# maido_board.net
KiCad netlist of a schematic drawn in EAGLE
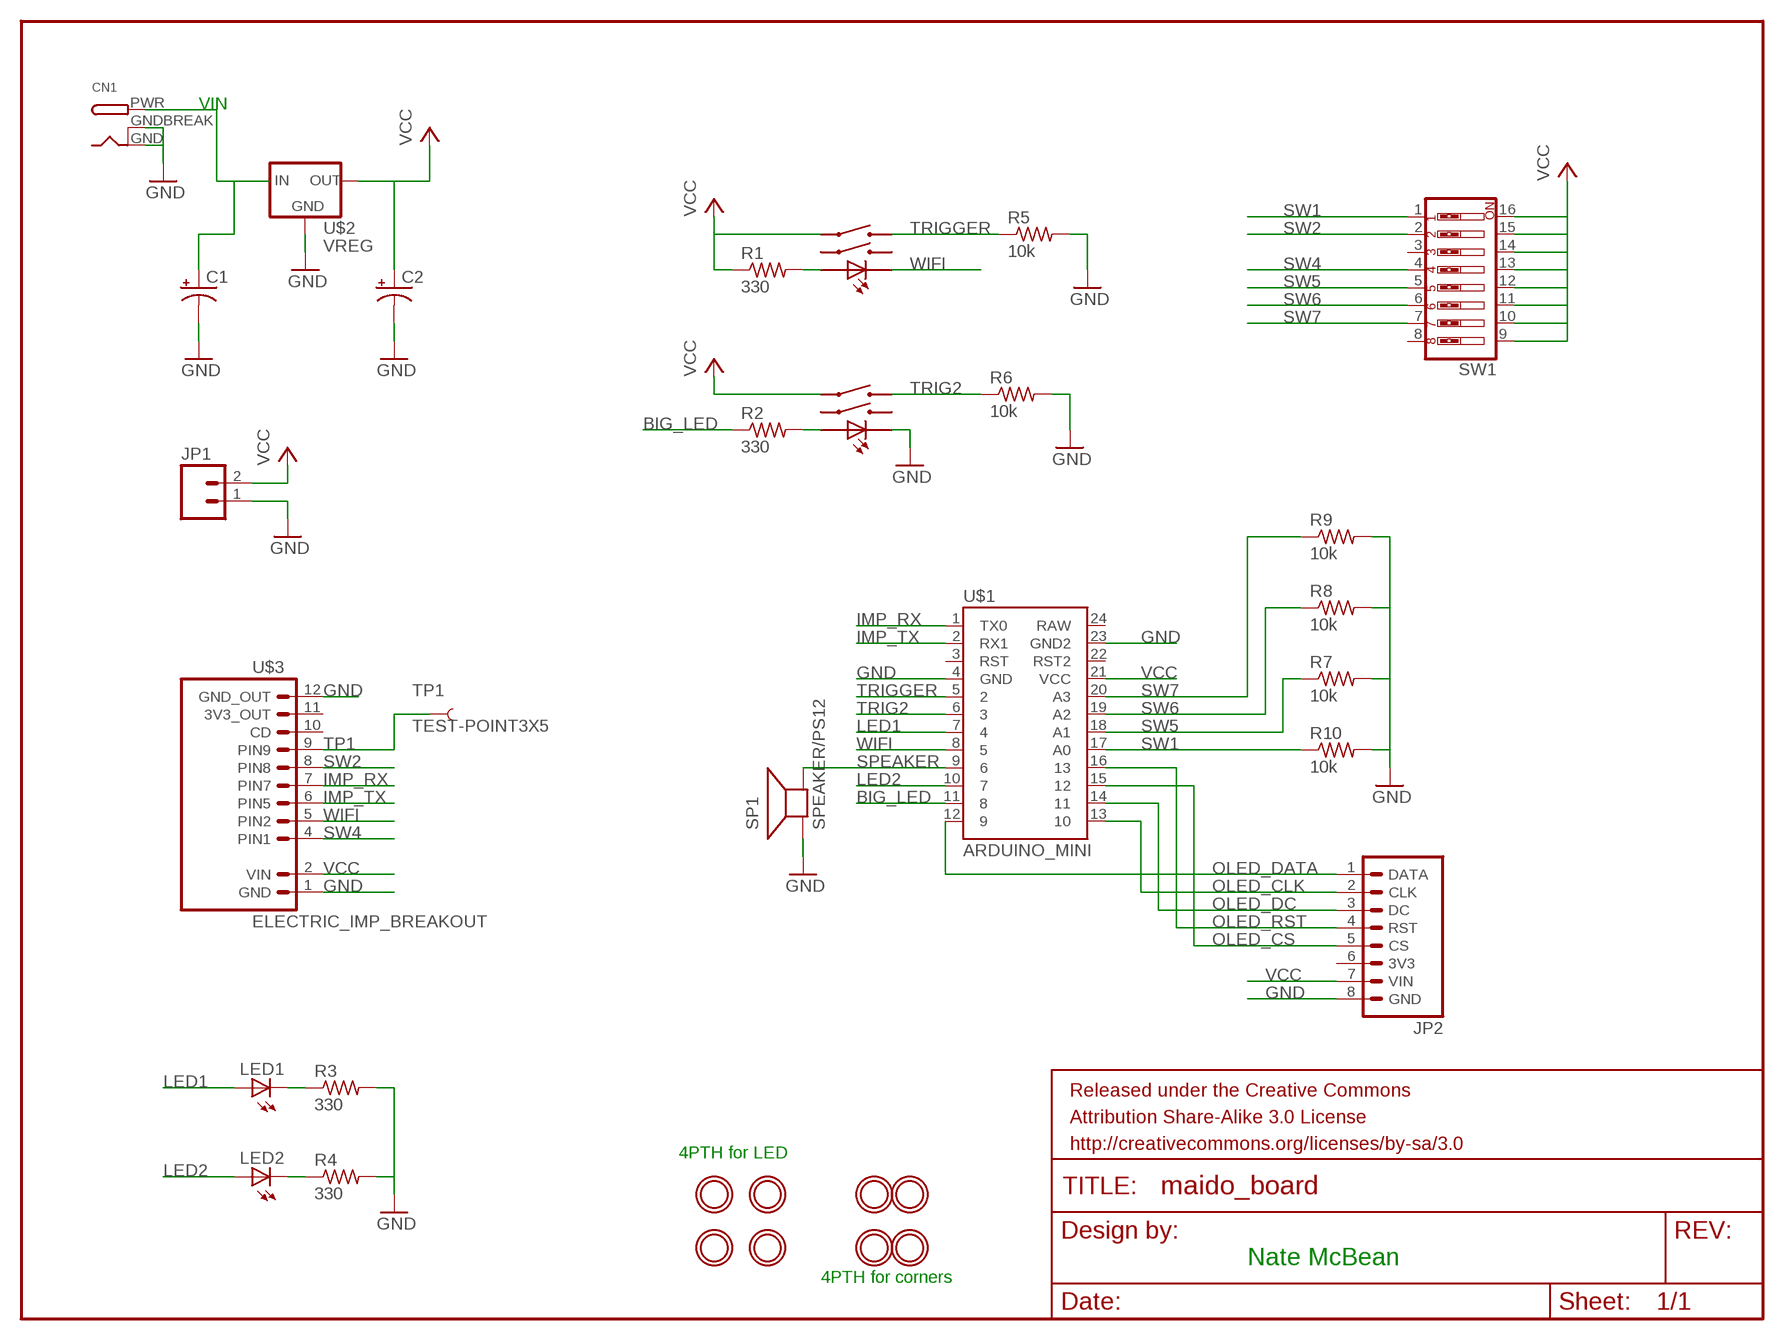
[diagram p0: schematic, sheet 1]

(export (version "E")
  (design (tool "Eeschema 10.0.6"))
  (components
    (comp (ref "ACK")
      (value "LED_TACTILE_BUTTON")
      (footprint "eagle-import:LED_TACTILE_BUTTON")
      (libsource (lib "eagle-import") (part "LED_TACTILE_BUTTON"))
    )
    (comp (ref "C1")
      (value "CAP_POLPTH2")
      (footprint "eagle-import:CPOL-RADIAL-10UF-25V")
      (libsource (lib "eagle-import") (part "CAP_POLPTH2"))
    )
    (comp (ref "C2")
      (value "CAP_POLPTH2")
      (footprint "eagle-import:CPOL-RADIAL-10UF-25V")
      (libsource (lib "eagle-import") (part "CAP_POLPTH2"))
    )
    (comp (ref "CN1")
      (value "DCBARRELPTH")
      (footprint "eagle-import:DCJACK_2MM_PTH")
      (libsource (lib "eagle-import") (part "DCBARRELPTH"))
    )
    (comp (ref "FRAME1")
      (value "FRAME-LETTER")
      (footprint "eagle-import:CREATIVE_COMMONS")
      (libsource (lib "eagle-import") (part "FRAME-LETTER"))
    )
    (comp (ref "JP1")
      (value "M02PTH")
      (footprint "eagle-import:1X02")
      (libsource (lib "eagle-import") (part "M02PTH"))
    )
    (comp (ref "JP2")
      (value "OLED128X641X08")
      (footprint "eagle-import:OLED_128X64")
      (libsource (lib "eagle-import") (part "OLED128X641X08"))
    )
    (comp (ref "LED1")
      (value "LED5MM")
      (footprint "eagle-import:LED5MM")
      (libsource (lib "eagle-import") (part "LED5MM"))
    )
    (comp (ref "LED2")
      (value "LED5MM")
      (footprint "eagle-import:LED5MM")
      (libsource (lib "eagle-import") (part "LED5MM"))
    )
    (comp (ref "R1")
      (value "330")
      (footprint "eagle-import:R0805")
      (libsource (lib "eagle-import") (part "R-US_R0805"))
    )
    (comp (ref "R2")
      (value "330")
      (footprint "eagle-import:R0805")
      (libsource (lib "eagle-import") (part "R-US_R0805"))
    )
    (comp (ref "R3")
      (value "330")
      (footprint "eagle-import:R0805")
      (libsource (lib "eagle-import") (part "R-US_R0805"))
    )
    (comp (ref "R4")
      (value "330")
      (footprint "eagle-import:R0805")
      (libsource (lib "eagle-import") (part "R-US_R0805"))
    )
    (comp (ref "R5")
      (value "10k")
      (footprint "eagle-import:R0805")
      (libsource (lib "eagle-import") (part "R-US_R0805"))
    )
    (comp (ref "R6")
      (value "10k")
      (footprint "eagle-import:R0805")
      (libsource (lib "eagle-import") (part "R-US_R0805"))
    )
    (comp (ref "R7")
      (value "10k")
      (footprint "eagle-import:R0805")
      (libsource (lib "eagle-import") (part "R-US_R0805"))
    )
    (comp (ref "R8")
      (value "10k")
      (footprint "eagle-import:R0805")
      (libsource (lib "eagle-import") (part "R-US_R0805"))
    )
    (comp (ref "R9")
      (value "10k")
      (footprint "eagle-import:R0805")
      (libsource (lib "eagle-import") (part "R-US_R0805"))
    )
    (comp (ref "R10")
      (value "10k")
      (footprint "eagle-import:R0805")
      (libsource (lib "eagle-import") (part "R-US_R0805"))
    )
    (comp (ref "SEND")
      (value "LED_TACTILE_BUTTON")
      (footprint "eagle-import:LED_TACTILE_BUTTON")
      (libsource (lib "eagle-import") (part "LED_TACTILE_BUTTON"))
    )
    (comp (ref "SP1")
      (value "SPEAKER/PS12")
      (footprint "eagle-import:PS12")
      (libsource (lib "eagle-import") (part "SPEAKER/PS12"))
    )
    (comp (ref "SW1")
      (value "SW_DIP-8")
      (footprint "eagle-import:DIPSWITCH-08")
      (libsource (lib "eagle-import") (part "SW_DIP-8"))
    )
    (comp (ref "TP1")
      (value "TEST-POINT3X5")
      (footprint "eagle-import:PAD.03X.05")
      (libsource (lib "eagle-import") (part "TEST-POINT3X5"))
    )
    (comp (ref "U$1")
      (value "ARDUINO_MINI")
      (footprint "eagle-import:ARDUINO_MINI")
      (libsource (lib "eagle-import") (part "ARDUINO_MINI"))
    )
    (comp (ref "U$2")
      (value "VREG")
      (footprint "eagle-import:78XXL")
      (libsource (lib "eagle-import") (part "V_REG_LD1117VXX"))
    )
    (comp (ref "U$3")
      (value "ELECTRIC_IMP_BREAKOUT")
      (footprint "eagle-import:ELECTRIC_IMP_BREAKOUT")
      (libsource (lib "eagle-import") (part "ELECTRIC_IMP_BREAKOUT"))
    )
    (comp (ref "U$5")
      (value "MOUNTINGHOLE2.5")
      (footprint "eagle-import:MOUNTINGHOLE_2.5_PLATED")
      (libsource (lib "eagle-import") (part "MOUNTINGHOLE2.5"))
    )
    (comp (ref "U$6")
      (value "MOUNTINGHOLE2.5")
      (footprint "eagle-import:MOUNTINGHOLE_2.5_PLATED")
      (libsource (lib "eagle-import") (part "MOUNTINGHOLE2.5"))
    )
    (comp (ref "U$7")
      (value "MOUNTINGHOLE2.5")
      (footprint "eagle-import:MOUNTINGHOLE_2.5_PLATED")
      (libsource (lib "eagle-import") (part "MOUNTINGHOLE2.5"))
    )
    (comp (ref "U$8")
      (value "MOUNTINGHOLE2.5")
      (footprint "eagle-import:MOUNTINGHOLE_2.5_PLATED")
      (libsource (lib "eagle-import") (part "MOUNTINGHOLE2.5"))
    )
    (comp (ref "U$9")
      (value "MOUNTINGHOLE2.5")
      (footprint "eagle-import:MOUNTINGHOLE_2.5_PLATED")
      (libsource (lib "eagle-import") (part "MOUNTINGHOLE2.5"))
    )
    (comp (ref "U$10")
      (value "MOUNTINGHOLE2.5")
      (footprint "eagle-import:MOUNTINGHOLE_2.5_PLATED")
      (libsource (lib "eagle-import") (part "MOUNTINGHOLE2.5"))
    )
    (comp (ref "U$11")
      (value "MOUNTINGHOLE2.5")
      (footprint "eagle-import:MOUNTINGHOLE_2.5_PLATED")
      (libsource (lib "eagle-import") (part "MOUNTINGHOLE2.5"))
    )
    (comp (ref "U$12")
      (value "MOUNTINGHOLE2.5")
      (footprint "eagle-import:MOUNTINGHOLE_2.5_PLATED")
      (libsource (lib "eagle-import") (part "MOUNTINGHOLE2.5"))
    )
  )
  (nets
    (net (code "1") (name "/BIG_LED") (class "Default")
      (node (ref "R2") (pin "1") (pinfunction "1_1") (pintype "passive"))
      (node (ref "U$1") (pin "11") (pinfunction "8_11") (pintype "bidirectional"))
    )
    (net (code "2") (name "/IMP_RX") (class "Default")
      (node (ref "U$1") (pin "1") (pinfunction "TX0_1") (pintype "bidirectional"))
      (node (ref "U$3") (pin "7") (pinfunction "PIN7_7") (pintype "passive"))
    )
    (net (code "3") (name "/IMP_TX") (class "Default")
      (node (ref "U$1") (pin "2") (pinfunction "RX1_2") (pintype "bidirectional"))
      (node (ref "U$3") (pin "6") (pinfunction "PIN5_6") (pintype "passive"))
    )
    (net (code "4") (name "/LED1") (class "Default")
      (node (ref "LED1") (pin "A") (pinfunction "A_A") (pintype "passive"))
      (node (ref "U$1") (pin "7") (pinfunction "4_7") (pintype "bidirectional"))
    )
    (net (code "5") (name "/LED2") (class "Default")
      (node (ref "LED2") (pin "A") (pinfunction "A_A") (pintype "passive"))
      (node (ref "U$1") (pin "10") (pinfunction "7_10") (pintype "bidirectional"))
    )
    (net (code "6") (name "/OLED_CLK") (class "Default")
      (node (ref "JP2") (pin "2") (pinfunction "CLK_2") (pintype "passive"))
      (node (ref "U$1") (pin "13") (pinfunction "10_13") (pintype "bidirectional"))
    )
    (net (code "7") (name "/OLED_CS") (class "Default")
      (node (ref "JP2") (pin "5") (pinfunction "CS_5") (pintype "passive"))
      (node (ref "U$1") (pin "15") (pinfunction "12_15") (pintype "bidirectional"))
    )
    (net (code "8") (name "/OLED_DATA") (class "Default")
      (node (ref "JP2") (pin "1") (pinfunction "DATA_1") (pintype "passive"))
      (node (ref "U$1") (pin "12") (pinfunction "9_12") (pintype "bidirectional"))
    )
    (net (code "9") (name "/OLED_DC") (class "Default")
      (node (ref "JP2") (pin "3") (pinfunction "DC_3") (pintype "passive"))
      (node (ref "U$1") (pin "14") (pinfunction "11_14") (pintype "bidirectional"))
    )
    (net (code "10") (name "/OLED_RST") (class "Default")
      (node (ref "JP2") (pin "4") (pinfunction "RST_4") (pintype "passive"))
      (node (ref "U$1") (pin "16") (pinfunction "13_16") (pintype "bidirectional"))
    )
    (net (code "11") (name "/SPEAKER") (class "Default")
      (node (ref "SP1") (pin "P$2") (pinfunction "-_P$2") (pintype "passive"))
      (node (ref "U$1") (pin "9") (pinfunction "6_9") (pintype "bidirectional"))
    )
    (net (code "12") (name "/SW1") (class "Default")
      (node (ref "R10") (pin "1") (pinfunction "1_1") (pintype "passive"))
      (node (ref "SW1") (pin "1") (pinfunction "1_1") (pintype "passive"))
      (node (ref "U$1") (pin "17") (pinfunction "A0_17") (pintype "bidirectional"))
    )
    (net (code "13") (name "/SW2") (class "Default")
      (node (ref "SW1") (pin "2") (pinfunction "2_2") (pintype "passive"))
      (node (ref "U$3") (pin "8") (pinfunction "PIN8_8") (pintype "passive"))
    )
    (net (code "14") (name "/SW4") (class "Default")
      (node (ref "SW1") (pin "4") (pinfunction "4_4") (pintype "passive"))
      (node (ref "U$3") (pin "4") (pinfunction "PIN1_4") (pintype "passive"))
    )
    (net (code "15") (name "/SW5") (class "Default")
      (node (ref "R7") (pin "1") (pinfunction "1_1") (pintype "passive"))
      (node (ref "SW1") (pin "5") (pinfunction "5_5") (pintype "passive"))
      (node (ref "U$1") (pin "18") (pinfunction "A1_18") (pintype "bidirectional"))
    )
    (net (code "16") (name "/SW6") (class "Default")
      (node (ref "R8") (pin "1") (pinfunction "1_1") (pintype "passive"))
      (node (ref "SW1") (pin "6") (pinfunction "6_6") (pintype "passive"))
      (node (ref "U$1") (pin "19") (pinfunction "A2_19") (pintype "bidirectional"))
    )
    (net (code "17") (name "/SW7") (class "Default")
      (node (ref "R9") (pin "1") (pinfunction "1_1") (pintype "passive"))
      (node (ref "SW1") (pin "7") (pinfunction "7_7") (pintype "passive"))
      (node (ref "U$1") (pin "20") (pinfunction "A3_20") (pintype "bidirectional"))
    )
    (net (code "18") (name "/TP1") (class "Default")
      (node (ref "TP1") (pin "P$1") (pinfunction "1_P$1") (pintype "bidirectional"))
      (node (ref "U$3") (pin "9") (pinfunction "PIN9_9") (pintype "passive"))
    )
    (net (code "19") (name "/TRIG2") (class "Default")
      (node (ref "ACK") (pin "SWA2") (pinfunction "SWA2_SWA2") (pintype "passive"))
      (node (ref "R6") (pin "1") (pinfunction "1_1") (pintype "passive"))
      (node (ref "U$1") (pin "6") (pinfunction "3_6") (pintype "bidirectional"))
    )
    (net (code "20") (name "/TRIGGER") (class "Default")
      (node (ref "R5") (pin "1") (pinfunction "1_1") (pintype "passive"))
      (node (ref "SEND") (pin "SWA2") (pinfunction "SWA2_SWA2") (pintype "passive"))
      (node (ref "U$1") (pin "5") (pinfunction "2_5") (pintype "bidirectional"))
    )
    (net (code "21") (name "/VIN") (class "Default")
      (node (ref "C1") (pin "1") (pinfunction "+_1") (pintype "passive"))
      (node (ref "CN1") (pin "PWR") (pinfunction "PWR_PWR") (pintype "power_in"))
      (node (ref "U$2") (pin "OUT") (pinfunction "IN_OUT") (pintype "input"))
    )
    (net (code "22") (name "/WIFI") (class "Default")
      (node (ref "SEND") (pin "LEDC") (pinfunction "LEDC_LEDC") (pintype "passive"))
      (node (ref "U$1") (pin "8") (pinfunction "5_8") (pintype "bidirectional"))
      (node (ref "U$3") (pin "5") (pinfunction "PIN2_5") (pintype "passive"))
    )
    (net (code "23") (name "GND") (class "Default")
      (node (ref "ACK") (pin "LEDC") (pinfunction "LEDC_LEDC") (pintype "passive"))
      (node (ref "C1") (pin "2") (pinfunction "-_2") (pintype "passive"))
      (node (ref "C2") (pin "2") (pinfunction "-_2") (pintype "passive"))
      (node (ref "CN1") (pin "GND") (pinfunction "GND_GND") (pintype "power_in"))
      (node (ref "CN1") (pin "GNDBREAK") (pinfunction "GNDBREAK_GNDBREAK") (pintype "power_in"))
      (node (ref "JP1") (pin "1") (pinfunction "1_1") (pintype "passive"))
      (node (ref "JP2") (pin "8") (pinfunction "GND_8") (pintype "passive"))
      (node (ref "R10") (pin "2") (pinfunction "2_2") (pintype "passive"))
      (node (ref "R3") (pin "2") (pinfunction "2_2") (pintype "passive"))
      (node (ref "R4") (pin "2") (pinfunction "2_2") (pintype "passive"))
      (node (ref "R5") (pin "2") (pinfunction "2_2") (pintype "passive"))
      (node (ref "R6") (pin "2") (pinfunction "2_2") (pintype "passive"))
      (node (ref "R7") (pin "2") (pinfunction "2_2") (pintype "passive"))
      (node (ref "R8") (pin "2") (pinfunction "2_2") (pintype "passive"))
      (node (ref "R9") (pin "2") (pinfunction "2_2") (pintype "passive"))
      (node (ref "SP1") (pin "P$1") (pinfunction "+_P$1") (pintype "passive"))
      (node (ref "U$1") (pin "23") (pinfunction "GND2_23") (pintype "bidirectional"))
      (node (ref "U$1") (pin "4") (pinfunction "GND_4") (pintype "bidirectional"))
      (node (ref "U$2") (pin "IN") (pinfunction "GND_IN") (pintype "input"))
      (node (ref "U$3") (pin "1") (pinfunction "GND_1") (pintype "passive"))
      (node (ref "U$3") (pin "12") (pinfunction "GND_OUT_12") (pintype "passive"))
    )
    (net (code "24") (name "Net-(ACK-PadLEDA)") (class "Default")
      (node (ref "ACK") (pin "LEDA") (pinfunction "LEDA_LEDA") (pintype "passive"))
      (node (ref "R2") (pin "2") (pinfunction "2_2") (pintype "passive"))
    )
    (net (code "25") (name "Net-(LED1-C)") (class "Default")
      (node (ref "LED1") (pin "K") (pinfunction "C_K") (pintype "passive"))
      (node (ref "R3") (pin "1") (pinfunction "1_1") (pintype "passive"))
    )
    (net (code "26") (name "Net-(LED2-C)") (class "Default")
      (node (ref "LED2") (pin "K") (pinfunction "C_K") (pintype "passive"))
      (node (ref "R4") (pin "1") (pinfunction "1_1") (pintype "passive"))
    )
    (net (code "27") (name "Net-(R1-Pad2)") (class "Default")
      (node (ref "R1") (pin "2") (pinfunction "2_2") (pintype "passive"))
      (node (ref "SEND") (pin "LEDA") (pinfunction "LEDA_LEDA") (pintype "passive"))
    )
    (net (code "28") (name "VCC") (class "Default")
      (node (ref "ACK") (pin "SWA1") (pinfunction "SWA1_SWA1") (pintype "passive"))
      (node (ref "C2") (pin "1") (pinfunction "+_1") (pintype "passive"))
      (node (ref "JP1") (pin "2") (pinfunction "2_2") (pintype "passive"))
      (node (ref "JP2") (pin "7") (pinfunction "VIN_7") (pintype "passive"))
      (node (ref "R1") (pin "1") (pinfunction "1_1") (pintype "passive"))
      (node (ref "SEND") (pin "SWA1") (pinfunction "SWA1_SWA1") (pintype "passive"))
      (node (ref "SW1") (pin "10") (pinfunction "10_10") (pintype "passive"))
      (node (ref "SW1") (pin "11") (pinfunction "11_11") (pintype "passive"))
      (node (ref "SW1") (pin "12") (pinfunction "12_12") (pintype "passive"))
      (node (ref "SW1") (pin "13") (pinfunction "13_13") (pintype "passive"))
      (node (ref "SW1") (pin "14") (pinfunction "14_14") (pintype "passive"))
      (node (ref "SW1") (pin "15") (pinfunction "15_15") (pintype "passive"))
      (node (ref "SW1") (pin "16") (pinfunction "16_16") (pintype "passive"))
      (node (ref "SW1") (pin "9") (pinfunction "9_9") (pintype "passive"))
      (node (ref "U$1") (pin "21") (pinfunction "VCC_21") (pintype "bidirectional"))
      (node (ref "U$2") (pin "GND") (pinfunction "OUT_GND") (pintype "output"))
      (node (ref "U$3") (pin "2") (pinfunction "VIN_2") (pintype "passive"))
    )
    (net (code "29") (name "unconnected-(ACK-PadSWB1)") (class "Default")
      (node (ref "ACK") (pin "SWB1") (pinfunction "SWB1_SWB1") (pintype "passive"))
    )
    (net (code "30") (name "unconnected-(ACK-PadSWB2)") (class "Default")
      (node (ref "ACK") (pin "SWB2") (pinfunction "SWB2_SWB2") (pintype "passive"))
    )
    (net (code "31") (name "unconnected-(JP2-3V3-Pad6)") (class "Default")
      (node (ref "JP2") (pin "6") (pinfunction "3V3_6") (pintype "passive"))
    )
    (net (code "32") (name "unconnected-(SEND-PadSWB1)") (class "Default")
      (node (ref "SEND") (pin "SWB1") (pinfunction "SWB1_SWB1") (pintype "passive"))
    )
    (net (code "33") (name "unconnected-(SEND-PadSWB2)") (class "Default")
      (node (ref "SEND") (pin "SWB2") (pinfunction "SWB2_SWB2") (pintype "passive"))
    )
    (net (code "34") (name "unconnected-(SW1-Pad3)") (class "Default")
      (node (ref "SW1") (pin "3") (pinfunction "3_3") (pintype "passive"))
    )
    (net (code "35") (name "unconnected-(SW1-Pad8)") (class "Default")
      (node (ref "SW1") (pin "8") (pinfunction "8_8") (pintype "passive"))
    )
    (net (code "36") (name "unconnected-(U$1-RAW-Pad24)") (class "Default")
      (node (ref "U$1") (pin "24") (pinfunction "RAW_24") (pintype "bidirectional"))
    )
    (net (code "37") (name "unconnected-(U$1-RST-Pad3)") (class "Default")
      (node (ref "U$1") (pin "3") (pinfunction "RST_3") (pintype "bidirectional"))
    )
    (net (code "38") (name "unconnected-(U$1-RST2-Pad22)") (class "Default")
      (node (ref "U$1") (pin "22") (pinfunction "RST2_22") (pintype "bidirectional"))
    )
    (net (code "39") (name "unconnected-(U$3-3V3_OUT-Pad11)") (class "Default")
      (node (ref "U$3") (pin "11") (pinfunction "3V3_OUT_11") (pintype "passive"))
    )
    (net (code "40") (name "unconnected-(U$3-CD-Pad10)") (class "Default")
      (node (ref "U$3") (pin "10") (pinfunction "CD_10") (pintype "passive"))
    )
  )
)
